# vssb_PTH.net
KiCad netlist of a schematic drawn in EAGLE
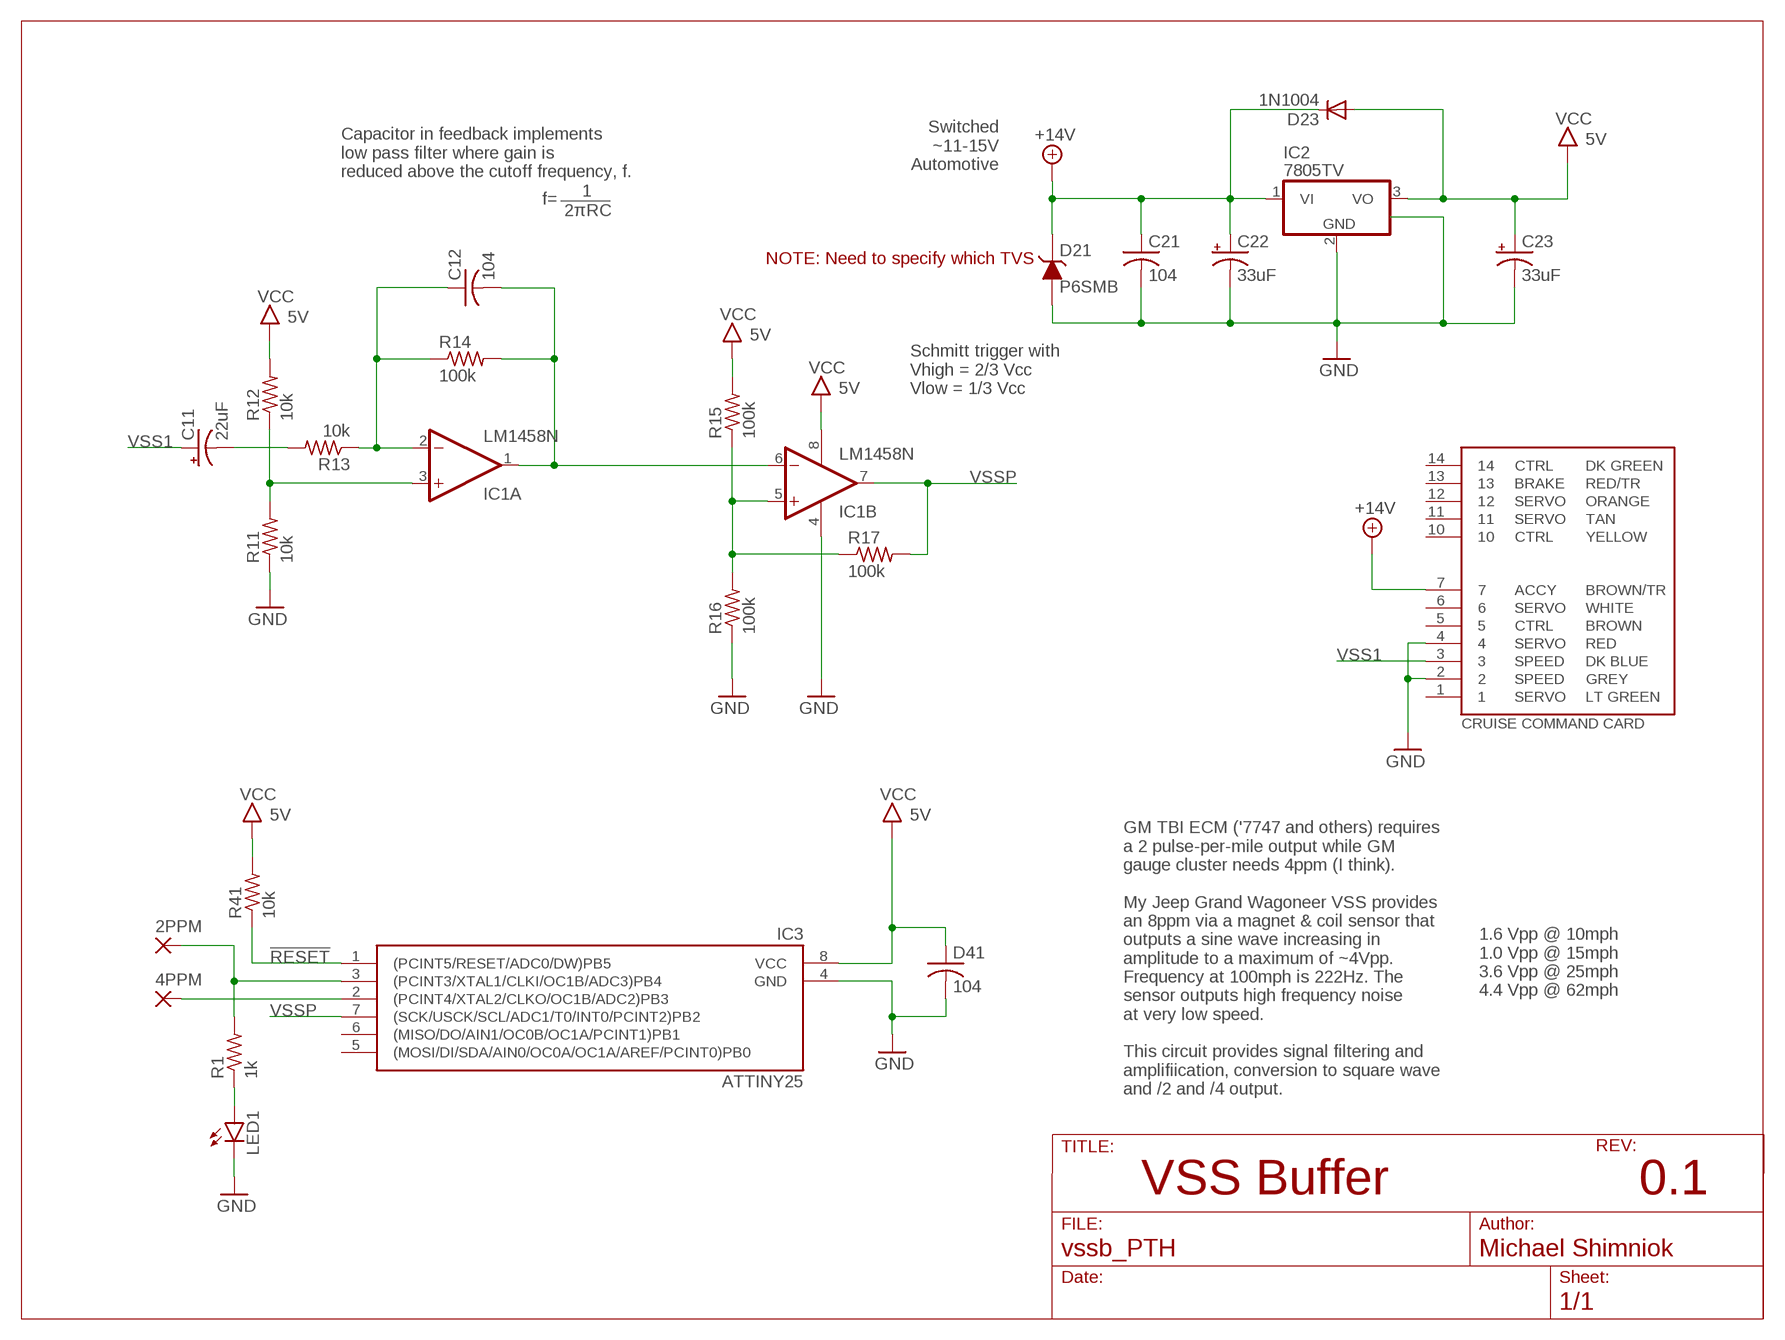
[diagram p0: schematic, sheet 1]

(export (version "E")
  (design (tool "Eeschema 10.0.6"))
  (components
    (comp (ref "2PPM")
      (value "WIREPAD3,17/1,3")
      (footprint "eagle-import:3,17_1,3")
      (libsource (lib "eagle-import") (part "WIREPAD3,17/1,3"))
    )
    (comp (ref "4PPM")
      (value "WIREPAD3,17/1,3")
      (footprint "eagle-import:3,17_1,3")
      (libsource (lib "eagle-import") (part "WIREPAD3,17/1,3"))
    )
    (comp (ref "C11")
      (value "22uF")
      (footprint "eagle-import:E5-5")
      (libsource (lib "eagle-import") (part "CPOL-USE5-5"))
    )
    (comp (ref "C12")
      (value "104")
      (footprint "eagle-import:C050-024X044")
      (libsource (lib "eagle-import") (part "C-US050-024X044"))
    )
    (comp (ref "C21")
      (value "104")
      (footprint "eagle-import:C050-024X044")
      (libsource (lib "eagle-import") (part "C-US050-024X044"))
    )
    (comp (ref "C22")
      (value "33uF")
      (footprint "eagle-import:E2,5-6")
      (libsource (lib "eagle-import") (part "CPOL-USE2.5-6"))
    )
    (comp (ref "C23")
      (value "33uF")
      (footprint "eagle-import:E2,5-6")
      (libsource (lib "eagle-import") (part "CPOL-USE2.5-6"))
    )
    (comp (ref "D21")
      (value "P6SMB")
      (footprint "eagle-import:DO-214AA")
      (libsource (lib "eagle-import") (part "P6SMBXXAT3GSMA"))
    )
    (comp (ref "D23")
      (value "1N1004")
      (footprint "eagle-import:DO41-10")
      (libsource (lib "eagle-import") (part "1N4004"))
    )
    (comp (ref "D41")
      (value "104")
      (footprint "eagle-import:C050-024X044")
      (libsource (lib "eagle-import") (part "C-US050-024X044"))
    )
    (comp (ref "IC1")
      (value "LM1458N")
      (footprint "eagle-import:DIL08")
      (libsource (lib "eagle-import") (part "1458NLM"))
    )
    (comp (ref "IC2")
      (value "7805TV")
      (footprint "eagle-import:TO220V")
      (libsource (lib "eagle-import") (part "78TV05"))
    )
    (comp (ref "IC3")
      (value "ATTINY25")
      (footprint "eagle-import:DIL08")
      (libsource (lib "eagle-import") (part "ATTINY45/85-MU"))
    )
    (comp (ref "LED1")
      (value "LED3MM")
      (footprint "eagle-import:LED3MM")
      (libsource (lib "eagle-import") (part "LED3MM"))
    )
    (comp (ref "R1")
      (value "1k")
      (footprint "eagle-import:0204_5")
      (libsource (lib "eagle-import") (part "R-US_0204/5"))
    )
    (comp (ref "R11")
      (value "10k")
      (footprint "eagle-import:0204_5")
      (libsource (lib "eagle-import") (part "R-US_0204/5"))
    )
    (comp (ref "R12")
      (value "10k")
      (footprint "eagle-import:0204_5")
      (libsource (lib "eagle-import") (part "R-US_0204/5"))
    )
    (comp (ref "R13")
      (value "10k")
      (footprint "eagle-import:0204_5")
      (libsource (lib "eagle-import") (part "R-US_0204/5"))
    )
    (comp (ref "R14")
      (value "100k")
      (footprint "eagle-import:0204_5")
      (libsource (lib "eagle-import") (part "R-US_0204/5"))
    )
    (comp (ref "R15")
      (value "100k")
      (footprint "eagle-import:0204_5")
      (libsource (lib "eagle-import") (part "R-US_0204/5"))
    )
    (comp (ref "R16")
      (value "100k")
      (footprint "eagle-import:0204_5")
      (libsource (lib "eagle-import") (part "R-US_0204/5"))
    )
    (comp (ref "R17")
      (value "100k")
      (footprint "eagle-import:0204_5")
      (libsource (lib "eagle-import") (part "R-US_0204/5"))
    )
    (comp (ref "R41")
      (value "10k")
      (footprint "eagle-import:0204_5")
      (libsource (lib "eagle-import") (part "R-US_0204/5"))
    )
    (comp (ref "U$4")
      (value "FSJ_CC_CARD")
      (footprint "eagle-import:FSJ_CC")
      (libsource (lib "eagle-import") (part "FSJ_CC_CARD"))
    )
  )
  (nets
    (net (code "1") (name "+14V") (class "Default")
      (node (ref "C21") (pin "1") (pinfunction "1_1") (pintype "passive"))
      (node (ref "C22") (pin "+") (pinfunction "+_+") (pintype "passive"))
      (node (ref "D21") (pin "P$1") (pinfunction "C_P$1") (pintype "passive"))
      (node (ref "D23") (pin "C") (pinfunction "C_C") (pintype "passive"))
      (node (ref "IC2") (pin "1") (pinfunction "VI_1") (pintype "input"))
      (node (ref "U$4") (pin "7") (pinfunction "7_7") (pintype "bidirectional"))
    )
    (net (code "2") (name "/VSS1") (class "Default")
      (node (ref "C11") (pin "+") (pinfunction "+_+") (pintype "passive"))
      (node (ref "U$4") (pin "3") (pinfunction "3_3") (pintype "bidirectional"))
    )
    (net (code "3") (name "/VSSP") (class "Default")
      (node (ref "IC1") (pin "7") (pinfunction "OUT_7") (pintype "output"))
      (node (ref "IC3") (pin "7") (pinfunction "(SCK/USCK/SCL/ADC1/T0/INT0/PCINT2)PB2_7") (pintype "bidirectional"))
      (node (ref "R17") (pin "2") (pinfunction "2_2") (pintype "passive"))
    )
    (net (code "4") (name "/~{RESET}") (class "Default")
      (node (ref "IC3") (pin "1") (pinfunction "(PCINT5/RESET/ADC0/DW)PB5_1") (pintype "bidirectional"))
      (node (ref "R41") (pin "1") (pinfunction "1_1") (pintype "passive"))
    )
    (net (code "5") (name "5V") (class "Default")
      (node (ref "C23") (pin "+") (pinfunction "+_+") (pintype "passive"))
      (node (ref "D23") (pin "A") (pinfunction "A_A") (pintype "passive"))
      (node (ref "D41") (pin "1") (pinfunction "1_1") (pintype "passive"))
      (node (ref "IC1") (pin "8") (pinfunction "V+_8") (pintype "power_in"))
      (node (ref "IC2") (pin "3") (pinfunction "VO_3") (pintype "passive"))
      (node (ref "IC3") (pin "8") (pinfunction "VCC_8") (pintype "power_in"))
      (node (ref "R12") (pin "2") (pinfunction "2_2") (pintype "passive"))
      (node (ref "R15") (pin "2") (pinfunction "2_2") (pintype "passive"))
      (node (ref "R41") (pin "2") (pinfunction "2_2") (pintype "passive"))
    )
    (net (code "6") (name "GND") (class "Default")
      (node (ref "C21") (pin "2") (pinfunction "2_2") (pintype "passive"))
      (node (ref "C22") (pin "-") (pinfunction "-_-") (pintype "passive"))
      (node (ref "C23") (pin "-") (pinfunction "-_-") (pintype "passive"))
      (node (ref "D21") (pin "P$2") (pinfunction "A_P$2") (pintype "passive"))
      (node (ref "D41") (pin "2") (pinfunction "2_2") (pintype "passive"))
      (node (ref "IC1") (pin "4") (pinfunction "V-_4") (pintype "power_in"))
      (node (ref "IC2") (pin "2") (pinfunction "GND_2") (pintype "passive"))
      (node (ref "IC3") (pin "4") (pinfunction "GND_4") (pintype "power_in"))
      (node (ref "LED1") (pin "K") (pinfunction "C_K") (pintype "passive"))
      (node (ref "R11") (pin "1") (pinfunction "1_1") (pintype "passive"))
      (node (ref "R16") (pin "1") (pinfunction "1_1") (pintype "passive"))
      (node (ref "U$4") (pin "2") (pinfunction "2_2") (pintype "bidirectional"))
      (node (ref "U$4") (pin "4") (pinfunction "4_4") (pintype "bidirectional"))
    )
    (net (code "7") (name "Net-(2PPM-P)") (class "Default")
      (node (ref "2PPM") (pin "1") (pinfunction "P_1") (pintype "passive"))
      (node (ref "IC3") (pin "3") (pinfunction "(PCINT3/XTAL1/CLKI/OC1B/ADC3)PB4_3") (pintype "bidirectional"))
      (node (ref "R1") (pin "2") (pinfunction "2_2") (pintype "passive"))
    )
    (net (code "8") (name "Net-(4PPM-P)") (class "Default")
      (node (ref "4PPM") (pin "1") (pinfunction "P_1") (pintype "passive"))
      (node (ref "IC3") (pin "2") (pinfunction "(PCINT4/XTAL2/CLKO/OC1B/ADC2)PB3_2") (pintype "bidirectional"))
    )
    (net (code "9") (name "Net-(C11-Pad-)") (class "Default")
      (node (ref "C11") (pin "-") (pinfunction "-_-") (pintype "passive"))
      (node (ref "R13") (pin "2") (pinfunction "2_2") (pintype "passive"))
    )
    (net (code "10") (name "Net-(IC1A-+IN)") (class "Default")
      (node (ref "IC1") (pin "3") (pinfunction "+IN_3") (pintype "input"))
      (node (ref "R11") (pin "2") (pinfunction "2_2") (pintype "passive"))
      (node (ref "R12") (pin "1") (pinfunction "1_1") (pintype "passive"))
    )
    (net (code "11") (name "Net-(IC1A--IN)") (class "Default")
      (node (ref "C12") (pin "1") (pinfunction "1_1") (pintype "passive"))
      (node (ref "IC1") (pin "2") (pinfunction "-IN_2") (pintype "input"))
      (node (ref "R13") (pin "1") (pinfunction "1_1") (pintype "passive"))
      (node (ref "R14") (pin "1") (pinfunction "1_1") (pintype "passive"))
    )
    (net (code "12") (name "Net-(IC1A-OUT)") (class "Default")
      (node (ref "C12") (pin "2") (pinfunction "2_2") (pintype "passive"))
      (node (ref "IC1") (pin "1") (pinfunction "OUT_1") (pintype "output"))
      (node (ref "IC1") (pin "6") (pinfunction "-IN_6") (pintype "input"))
      (node (ref "R14") (pin "2") (pinfunction "2_2") (pintype "passive"))
    )
    (net (code "13") (name "Net-(IC1B-+IN)") (class "Default")
      (node (ref "IC1") (pin "5") (pinfunction "+IN_5") (pintype "input"))
      (node (ref "R15") (pin "1") (pinfunction "1_1") (pintype "passive"))
      (node (ref "R16") (pin "2") (pinfunction "2_2") (pintype "passive"))
      (node (ref "R17") (pin "1") (pinfunction "1_1") (pintype "passive"))
    )
    (net (code "14") (name "Net-(LED1-PadA)") (class "Default")
      (node (ref "LED1") (pin "A") (pinfunction "A_A") (pintype "passive"))
      (node (ref "R1") (pin "1") (pinfunction "1_1") (pintype "passive"))
    )
    (net (code "15") (name "unconnected-(IC3-(MISO{slash}DO{slash}AIN1{slash}OC0B{slash}OC1A{slash}PCINT1)PB1-Pad6)") (class "Default")
      (node (ref "IC3") (pin "6") (pinfunction "(MISO/DO/AIN1/OC0B/OC1A/PCINT1)PB1_6") (pintype "bidirectional"))
    )
    (net (code "16") (name "unconnected-(IC3-(MOSI{slash}DI{slash}SDA{slash}AIN0{slash}OC0A{slash}OC1A{slash}AREF{slash}PCINT0)PB0-Pad5)") (class "Default")
      (node (ref "IC3") (pin "5") (pinfunction "(MOSI/DI/SDA/AIN0/OC0A/OC1A/AREF/PCINT0)PB0_5") (pintype "bidirectional"))
    )
    (net (code "17") (name "unconnected-(U$4-Pad1)") (class "Default")
      (node (ref "U$4") (pin "1") (pinfunction "1_1") (pintype "bidirectional"))
    )
    (net (code "18") (name "unconnected-(U$4-Pad5)") (class "Default")
      (node (ref "U$4") (pin "5") (pinfunction "5_5") (pintype "bidirectional"))
    )
    (net (code "19") (name "unconnected-(U$4-Pad6)") (class "Default")
      (node (ref "U$4") (pin "6") (pinfunction "6_6") (pintype "bidirectional"))
    )
    (net (code "20") (name "unconnected-(U$4-Pad10)") (class "Default")
      (node (ref "U$4") (pin "10") (pinfunction "10_10") (pintype "bidirectional"))
    )
    (net (code "21") (name "unconnected-(U$4-Pad11)") (class "Default")
      (node (ref "U$4") (pin "11") (pinfunction "11_11") (pintype "bidirectional"))
    )
    (net (code "22") (name "unconnected-(U$4-Pad12)") (class "Default")
      (node (ref "U$4") (pin "12") (pinfunction "12_12") (pintype "bidirectional"))
    )
    (net (code "23") (name "unconnected-(U$4-Pad13)") (class "Default")
      (node (ref "U$4") (pin "13") (pinfunction "13_13") (pintype "bidirectional"))
    )
    (net (code "24") (name "unconnected-(U$4-Pad14)") (class "Default")
      (node (ref "U$4") (pin "14") (pinfunction "14_14") (pintype "bidirectional"))
    )
  )
)
